# Power.net
KiCad netlist of a schematic drawn in EAGLE
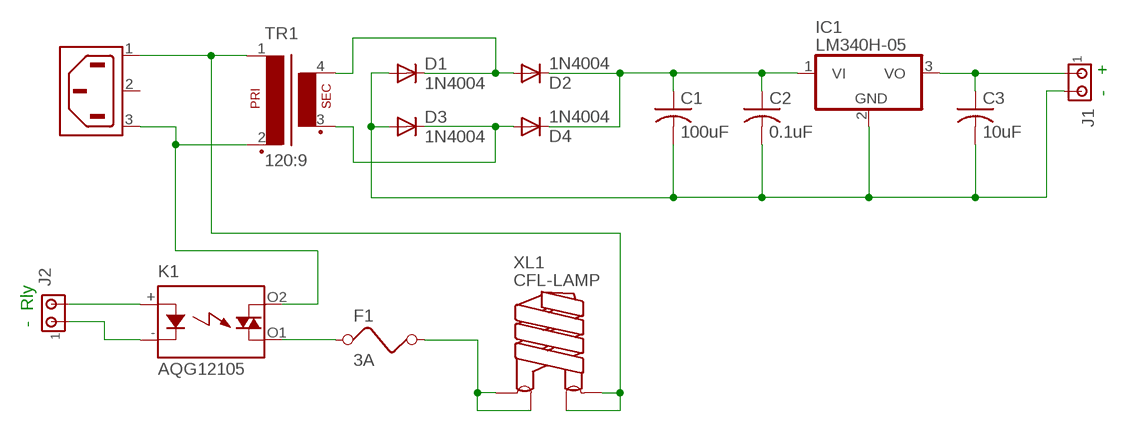
[diagram p0: schematic, sheet 1]

(export (version "E")
  (design (tool "Eeschema 10.0.6"))
  (components
    (comp (ref "C1")
      (value "100uF")
      (footprint "eagle-import:C075-032X103")
      (libsource (lib "eagle-import") (part "C-US075-032X103"))
    )
    (comp (ref "C2")
      (value "0.1uF")
      (footprint "eagle-import:C075-032X103")
      (libsource (lib "eagle-import") (part "C-US075-032X103"))
    )
    (comp (ref "C3")
      (value "10uF")
      (footprint "eagle-import:C075-032X103")
      (libsource (lib "eagle-import") (part "C-US075-032X103"))
    )
    (comp (ref "D1")
      (value "1N4004")
      (footprint "eagle-import:DO41-10")
      (libsource (lib "eagle-import") (part "1N4004"))
    )
    (comp (ref "D2")
      (value "1N4004")
      (footprint "eagle-import:DO41-10")
      (libsource (lib "eagle-import") (part "1N4004"))
    )
    (comp (ref "D3")
      (value "1N4004")
      (footprint "eagle-import:DO41-10")
      (libsource (lib "eagle-import") (part "1N4004"))
    )
    (comp (ref "D4")
      (value "1N4004")
      (footprint "eagle-import:DO41-10")
      (libsource (lib "eagle-import") (part "1N4004"))
    )
    (comp (ref "F1")
      (value "3A")
      (footprint "eagle-import:FUSE")
      (libsource (lib "eagle-import") (part "FUSE"))
    )
    (comp (ref "IC1")
      (value "LM340H-05")
      (footprint "eagle-import:TO220H")
      (libsource (lib "eagle-import") (part "LM340?-H05"))
    )
    (comp (ref "J1")
      (value "MTA02-100")
      (footprint "eagle-import:10X02MTA")
      (libsource (lib "eagle-import") (part "MTA02-100"))
    )
    (comp (ref "J2")
      (value "MTA02-100")
      (footprint "eagle-import:10X02MTA")
      (libsource (lib "eagle-import") (part "MTA02-100"))
    )
    (comp (ref "K1")
      (value "AQG12105")
      (footprint "eagle-import:AQG")
      (fields (field (name "MF") "AROMAT/ MATSUSHITA"))
      (libsource (lib "eagle-import") (part "AQG12105"))
    )
    (comp (ref "TR1")
      (value "120:9")
      (footprint "eagle-import:VP31")
      (libsource (lib "eagle-import") (part "VP31"))
    )
    (comp (ref "X1")
      (value "6ESRM-P")
      (footprint "eagle-import:6ESRM-P")
      (fields (field (name "MF") "TYCO ELECTRONICS"))
      (libsource (lib "eagle-import") (part "6ESRM-P"))
    )
    (comp (ref "XL1")
      (value "CFL-LAMP")
      (footprint "eagle-import:CFL-LAMP")
      (libsource (lib "eagle-import") (part "CFL-LAMP"))
    )
  )
  (nets
    (net (code "1") (name "Net-(F1-Pad2)") (class "Default")
      (node (ref "F1") (pin "2") (pinfunction "2_2") (pintype "passive"))
      (node (ref "XL1") (pin "1") (pinfunction "1_1") (pintype "passive"))
      (node (ref "XL1") (pin "3") (pinfunction "3_3") (pintype "passive"))
    )
    (net (code "2") (name "Net-(IC1-GND)") (class "Default")
      (node (ref "C1") (pin "2") (pinfunction "2_2") (pintype "passive"))
      (node (ref "C2") (pin "2") (pinfunction "2_2") (pintype "passive"))
      (node (ref "C3") (pin "2") (pinfunction "2_2") (pintype "passive"))
      (node (ref "D1") (pin "A") (pinfunction "A_A") (pintype "passive"))
      (node (ref "D3") (pin "A") (pinfunction "A_A") (pintype "passive"))
      (node (ref "IC1") (pin "2") (pinfunction "GND_2") (pintype "passive"))
      (node (ref "J1") (pin "2") (pinfunction "2_2") (pintype "passive"))
    )
    (net (code "3") (name "Net-(IC1-VI)") (class "Default")
      (node (ref "C1") (pin "1") (pinfunction "1_1") (pintype "passive"))
      (node (ref "C2") (pin "1") (pinfunction "1_1") (pintype "passive"))
      (node (ref "D2") (pin "C") (pinfunction "C_C") (pintype "passive"))
      (node (ref "D4") (pin "C") (pinfunction "C_C") (pintype "passive"))
      (node (ref "IC1") (pin "1") (pinfunction "VI_1") (pintype "input"))
    )
    (net (code "4") (name "Net-(IC1-VO)") (class "Default")
      (node (ref "C3") (pin "1") (pinfunction "1_1") (pintype "passive"))
      (node (ref "IC1") (pin "3") (pinfunction "VO_3") (pintype "passive"))
      (node (ref "J1") (pin "1") (pinfunction "1_1") (pintype "passive"))
    )
    (net (code "5") (name "Net-(K1-A)") (class "Default")
      (node (ref "J2") (pin "2") (pinfunction "2_2") (pintype "passive"))
      (node (ref "K1") (pin "+") (pinfunction "A_+") (pintype "passive"))
    )
    (net (code "6") (name "Net-(K1-DS1)") (class "Default")
      (node (ref "K1") (pin "O2") (pinfunction "DS1_O2") (pintype "passive"))
      (node (ref "TR1") (pin "2") (pinfunction "P2_2") (pintype "passive"))
      (node (ref "X1") (pin "3") (pinfunction "AC2_3") (pintype "passive"))
    )
    (net (code "7") (name "Net-(K1-DS2)") (class "Default")
      (node (ref "F1") (pin "1") (pinfunction "1_1") (pintype "passive"))
      (node (ref "K1") (pin "O1") (pinfunction "DS2_O1") (pintype "passive"))
    )
    (net (code "8") (name "Net-(K1-K)") (class "Default")
      (node (ref "J2") (pin "1") (pinfunction "1_1") (pintype "passive"))
      (node (ref "K1") (pin "-") (pinfunction "K_-") (pintype "passive"))
    )
    (net (code "9") (name "Net-(TR1-P1)") (class "Default")
      (node (ref "TR1") (pin "1") (pinfunction "P1_1") (pintype "passive"))
      (node (ref "X1") (pin "1") (pinfunction "AC1_1") (pintype "passive"))
      (node (ref "XL1") (pin "2") (pinfunction "2_2") (pintype "passive"))
      (node (ref "XL1") (pin "4") (pinfunction "4_4") (pintype "passive"))
    )
    (net (code "10") (name "Net-(TR1-S3)") (class "Default")
      (node (ref "D3") (pin "C") (pinfunction "C_C") (pintype "passive"))
      (node (ref "D4") (pin "A") (pinfunction "A_A") (pintype "passive"))
      (node (ref "TR1") (pin "3") (pinfunction "S3_3") (pintype "passive"))
    )
    (net (code "11") (name "Net-(TR1-S4)") (class "Default")
      (node (ref "D1") (pin "C") (pinfunction "C_C") (pintype "passive"))
      (node (ref "D2") (pin "A") (pinfunction "A_A") (pintype "passive"))
      (node (ref "TR1") (pin "4") (pinfunction "S4_4") (pintype "passive"))
    )
    (net (code "12") (name "unconnected-(X1-SH-Pad2)") (class "Default")
      (node (ref "X1") (pin "2") (pinfunction "SH_2") (pintype "passive"))
    )
  )
)
